# comms_interface.net
KiCad netlist of a schematic drawn in Altium Designer
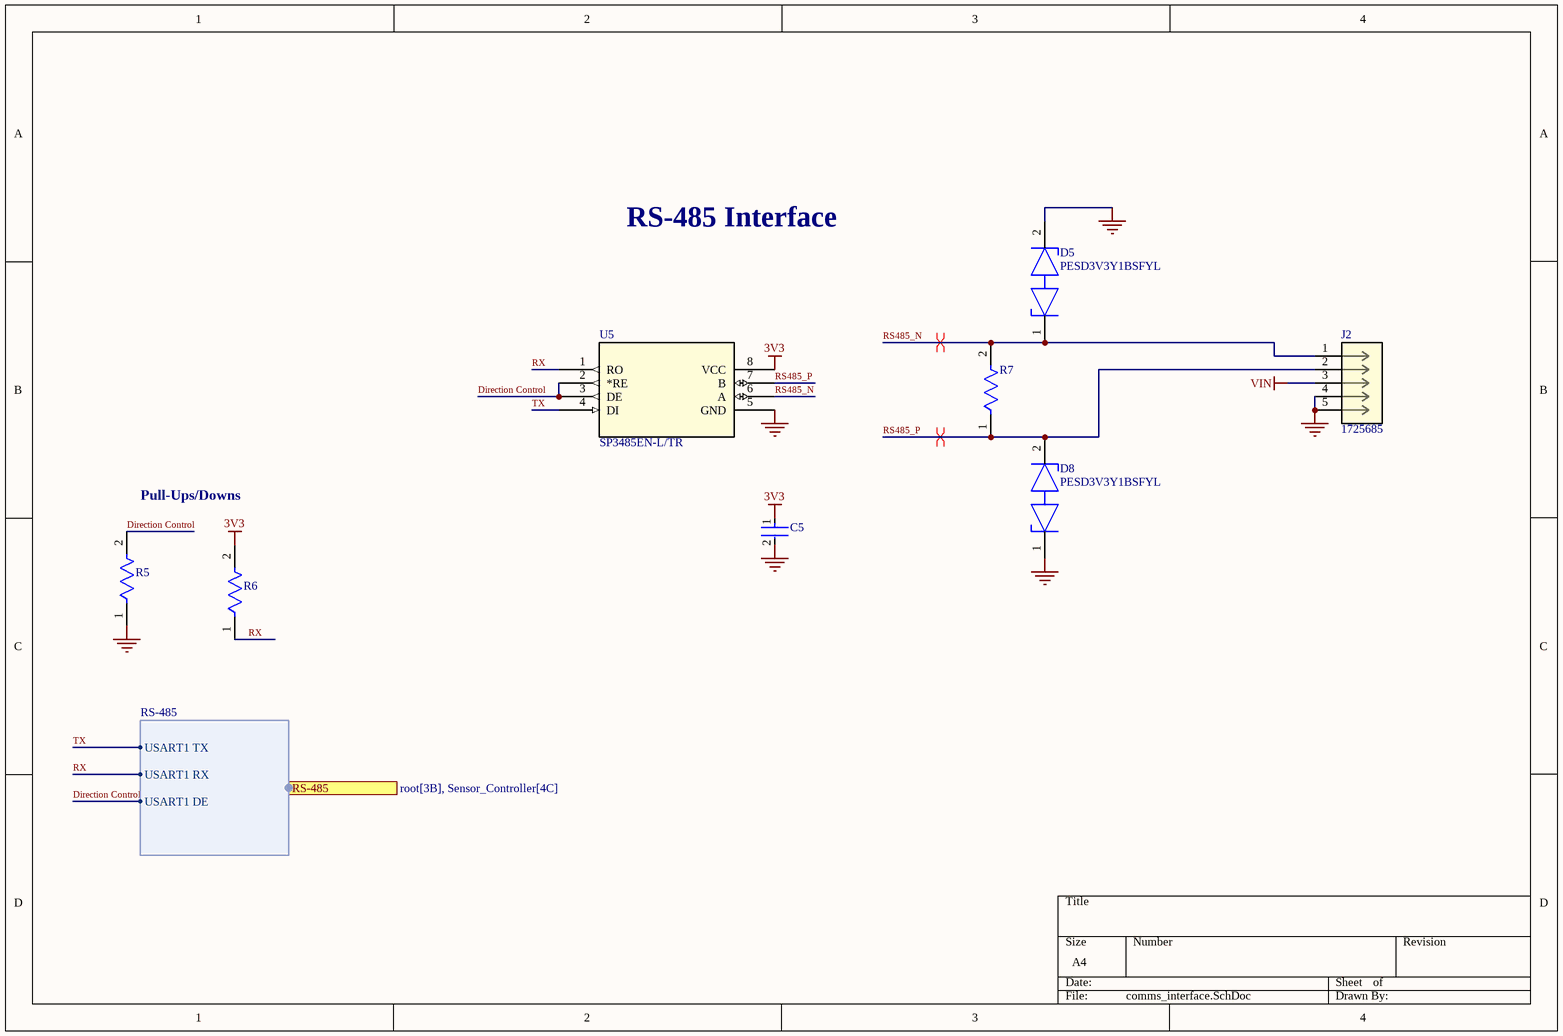
[diagram p0: comms_interface.SchDoc]

(export (version "E")
  (design (tool "Eeschema 10.0.6"))
  (components
    (comp (ref "C5")
      (value "LMK105B7104KVHF")
      (footprint "FP-0402-L_1_0_0_05-W_0_5-IPC_B")
      (description "None")
      (fields (field (name "TOLERANCE") "10%"))
      (libsource (lib "Altium Content Vault") (part "b4654b650e69147ec39a6b967a45e02"))
    )
    (comp (ref "D5")
      (value "PESD3V3Y1BSFYL")
      (footprint "FP-SOD962-2-CA-MFG")
      (description "PESD3V3Y1BSFYL PESD4V0Y1BSF - Extremely low capacitance bidirectional ESD protection diode")
      (libsource (lib "Altium Content Vault") (part "3f15ade4c48aeaca3578241bea7d4a4"))
    )
    (comp (ref "D8")
      (value "PESD3V3Y1BSFYL")
      (footprint "FP-SOD962-2-CA-MFG")
      (description "PESD3V3Y1BSFYL PESD4V0Y1BSF - Extremely low capacitance bidirectional ESD protection diode")
      (libsource (lib "Altium Content Vault") (part "3f15ade4c48aeaca3578241bea7d4a4"))
    )
    (comp (ref "J2")
      (value "1725685")
      (footprint "CONN_1725685_PXC")
      (fields (field (name "COPYRIGHT") "Copyright (C) 2026 Ultra Librarian. All rights reserved."))
      (libsource (lib "1725685") (part "1725685"))
    )
    (comp (ref "R5")
      (value "AF0402FR-073K3L")
      (footprint "FP-AF0402-IPC_B")
      (description "Anti-Sulfurated Chip Resistors Automotive Grade 3.3kΩ 1% 100ppm/°C 0402")
      (fields (field (name "TOLERANCE") "1%"))
      (libsource (lib "Altium Content Vault") (part "1029c3af85768c4190bb7ad29bc67b5"))
    )
    (comp (ref "R6")
      (value "AF0402FR-073K3L")
      (footprint "FP-AF0402-IPC_B")
      (description "Anti-Sulfurated Chip Resistors Automotive Grade 3.3kΩ 1% 100ppm/°C 0402")
      (fields (field (name "TOLERANCE") "1%"))
      (libsource (lib "Altium Content Vault") (part "1029c3af85768c4190bb7ad29bc67b5"))
    )
    (comp (ref "R7")
      (value "AF0402FR-07120RL")
      (footprint "FP-AF0402-IPC_A")
      (description "Anti-Sulfurated Chip Resistors Automotive Grade 120Ω 1% 100ppm/°C 0402")
      (fields (field (name "TOLERANCE") "1%"))
      (libsource (lib "Altium Content Vault") (part "1029c3af85768c4190bb7ad29bc67b5"))
    )
    (comp (ref "U5")
      (value "SP3485EN-L/TR")
      (footprint "NSOIC-8")
      (description "No Description Available")
      (fields (field (name "COPYRIGHT") "Copyright (C) 2026 Ultra Librarian. All rights reserved."))
      (libsource (lib "SP3485EN-LTR") (part "SP3485EN-LTR"))
    )
  )
  (nets
    (net (code "2") (name "/Direction Control") (class "Default")
      (node (ref "R5") (pin "2") (pinfunction "2_2") (pintype "passive"))
      (node (ref "U5") (pin "2") (pinfunction "*RE_2") (pintype "output"))
      (node (ref "U5") (pin "3") (pinfunction "DE_3") (pintype "output"))
    )
    (net (code "3") (name "/RS485_N") (class "Default")
      (node (ref "D5") (pin "1") (pinfunction "1_1") (pintype "passive"))
      (node (ref "J2") (pin "1") (pinfunction "1_1") (pintype "passive"))
      (node (ref "R7") (pin "2") (pinfunction "2_2") (pintype "passive"))
      (node (ref "U5") (pin "6") (pinfunction "A_6") (pintype "bidirectional"))
    )
    (net (code "4") (name "/RS485_P") (class "Default")
      (node (ref "D8") (pin "2") (pinfunction "2_2") (pintype "passive"))
      (node (ref "J2") (pin "2") (pinfunction "2_2") (pintype "passive"))
      (node (ref "R7") (pin "1") (pinfunction "1_1") (pintype "passive"))
      (node (ref "U5") (pin "7") (pinfunction "B_7") (pintype "bidirectional"))
    )
    (net (code "5") (name "/RX") (class "Default")
      (node (ref "R6") (pin "1") (pinfunction "1_1") (pintype "passive"))
      (node (ref "U5") (pin "1") (pinfunction "RO_1") (pintype "output"))
    )
    (net (code "6") (name "/TX") (class "Default")
      (node (ref "U5") (pin "4") (pinfunction "DI_4") (pintype "input"))
    )
    (net (code "8") (name "3V3") (class "Default")
      (node (ref "C5") (pin "1") (pinfunction "1_1") (pintype "passive"))
      (node (ref "R6") (pin "2") (pinfunction "2_2") (pintype "passive"))
      (node (ref "U5") (pin "8") (pinfunction "VCC_8") (pintype "power_in"))
    )
    (net (code "9") (name "GND") (class "Default")
      (node (ref "C5") (pin "2") (pinfunction "2_2") (pintype "passive"))
      (node (ref "D5") (pin "2") (pinfunction "2_2") (pintype "passive"))
      (node (ref "D8") (pin "1") (pinfunction "1_1") (pintype "passive"))
      (node (ref "J2") (pin "4") (pinfunction "4_4") (pintype "passive"))
      (node (ref "J2") (pin "5") (pinfunction "5_5") (pintype "passive"))
      (node (ref "R5") (pin "1") (pinfunction "1_1") (pintype "passive"))
      (node (ref "U5") (pin "5") (pinfunction "GND_5") (pintype "power_in"))
    )
    (net (code "10") (name "VIN") (class "Default")
      (node (ref "J2") (pin "3") (pinfunction "3_3") (pintype "passive"))
    )
  )
)
